# DC-DC_-5V.net
KiCad netlist of a schematic drawn in Altium Designer
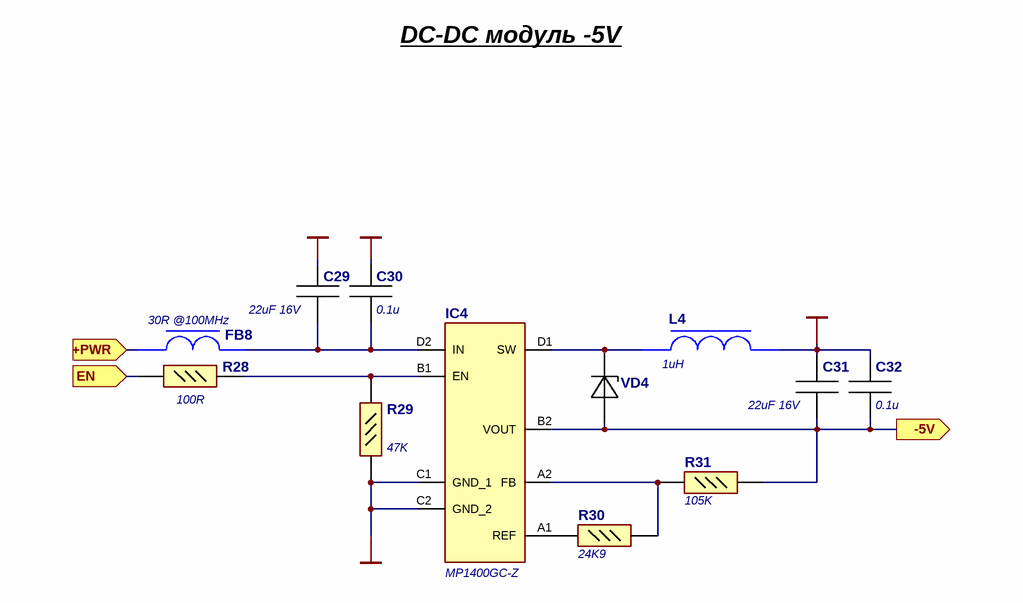
[diagram p0: DC-DC модуль -5V.SchDoc]

(export (version "E")
  (design (tool "Eeschema 10.0.6"))
  (components
    (comp (ref "C29")
      (value "22uF 16V")
      (footprint ":CAP0805 C2012X125")
      (description "CAP CER 22uF 16V X5R")
      (fields
        (field (name "MANUFACTURER_PART_NUMBER") "GRM21BR61C226ME44L")
        (field (name "MOUSER PART NUMBER") "81-GRM21BR61C226ME4L")
      )
      (libsource (lib "Capacitors 0805") (part "GRM21BR61C226ME44L"))
    )
    (comp (ref "C30")
      (value "0.1u")
      (footprint ":CAP0402 100x50x50")
      (description "±10% 25V Ceramic Capacitor X7R 0402 (1005 Metric)")
      (fields
        (field (name "MANUFACTURER_PART_NUMBER") "GRM155R71E104KE14J")
        (field (name "MOUSER PART NUMBER") "81-GRM155R71E104KE4J")
      )
      (libsource (lib "Capacitors 0402") (part "GRM155R71E104KE14J"))
    )
    (comp (ref "C31")
      (value "22uF 16V")
      (footprint ":CAP0805 C2012X125")
      (description "CAP CER 22uF 16V X5R")
      (fields
        (field (name "MANUFACTURER_PART_NUMBER") "GRM21BR61C226ME44L")
        (field (name "MOUSER PART NUMBER") "81-GRM21BR61C226ME4L")
      )
      (libsource (lib "Capacitors 0805") (part "GRM21BR61C226ME44L"))
    )
    (comp (ref "C32")
      (value "0.1u")
      (footprint ":CAP0402 100x50x50")
      (description "±10% 25V Ceramic Capacitor X7R 0402 (1005 Metric)")
      (fields
        (field (name "MANUFACTURER_PART_NUMBER") "GRM155R71E104KE14J")
        (field (name "MOUSER PART NUMBER") "81-GRM155R71E104KE4J")
      )
      (libsource (lib "Capacitors 0402") (part "GRM155R71E104KE14J"))
    )
    (comp (ref "FB8")
      (value "30R @100MHz")
      (footprint ":FER BLM18SP300SN1D")
      (description "30 Ohms @ 100MHz 1 Power Line Ferrite Bead 0603 (1608 Metric) 6A 8mOhm")
      (fields
        (field (name "MANUFACTURER_PART_NUMBER") "BLM18SP300SN1D")
        (field (name "MOUSER PART NUMBER") "81-BLM18SP300SN1D")
      )
      (libsource (lib "Ferrite Bead") (part "BLM18SP300SN1D"))
    )
    (comp (ref "IC4")
      (value "MP1400GC-Z")
      (footprint ":BGA8 CSP P2X4_80X160X63")
      (description "DC/DC Converter \r\nInput 2.7V...7V\r\nOutput -0.9V...-6V 600mA")
      (libsource (lib "DC-DC convertors") (part "MP1400GC-Z"))
    )
    (comp (ref "L4")
      (value "1uH")
      (footprint ":IND1210 C3225")
      (fields (field (name "MANUFACTURER_PART_NUMBER") "74479299210"))
      (libsource (lib "Inductance") (part "74479299210"))
    )
    (comp (ref "R28")
      (value "RC0402FR-07")
      (footprint ":RES0402")
      (fields (field (name "MANUFACTURER_PART_NUMBER (PART 2: VALUE)") "100R"))
      (libsource (lib "") (part "RC0402FR-07_1"))
    )
    (comp (ref "R29")
      (value "RC0402FR-07")
      (footprint ":RES0402")
      (fields (field (name "MANUFACTURER_PART_NUMBER (PART 2: VALUE)") "47K"))
      (libsource (lib "Resistors 0402") (part "RC0402FR-07"))
    )
    (comp (ref "R30")
      (value "RC0402FR-07")
      (footprint ":RES0402")
      (fields (field (name "MANUFACTURER_PART_NUMBER (PART 2: VALUE)") "24K9"))
      (libsource (lib "") (part "RC0402FR-07_1"))
    )
    (comp (ref "R31")
      (value "RC0402FR-07")
      (footprint ":RES0402")
      (fields (field (name "MANUFACTURER_PART_NUMBER (PART 2: VALUE)") "105K"))
      (libsource (lib "") (part "RC0402FR-07_1"))
    )
    (comp (ref "VD4")
      (value "40V 1.5A")
      (footprint ":DIODE CST2C")
      (description "Diode Schottky 40V 1.5A\r\n@If 550mV @ 1.5A\r\n@Vr 200µA @ 40V")
      (fields (field (name "MANUFACTURER_PART_NUMBER") "CCS15S40,L3F"))
      (libsource (lib "Diodes 0603") (part "CCS15S40,L3F"))
    )
  )
  (nets
    (net (code "1") (name "/+PWR") (class "Default")
      (node (ref "FB8") (pin "1") (pinfunction "1_1") (pintype "passive"))
    )
    (net (code "2") (name "/-5V") (class "Default")
      (node (ref "C31") (pin "1") (pinfunction "1_1") (pintype "passive"))
      (node (ref "C32") (pin "2") (pinfunction "2_2") (pintype "passive"))
      (node (ref "IC4") (pin "B2") (pinfunction "VOUT_B2") (pintype "passive"))
      (node (ref "R31") (pin "2") (pinfunction "2_2") (pintype "passive"))
      (node (ref "VD4") (pin "2") (pinfunction "A_2") (pintype "passive"))
    )
    (net (code "3") (name "/EN") (class "Default")
      (node (ref "R28") (pin "1") (pinfunction "1_1") (pintype "passive"))
    )
    (net (code "4") (name "GND") (class "Default")
      (node (ref "C29") (pin "2") (pinfunction "2_2") (pintype "passive"))
      (node (ref "C30") (pin "1") (pinfunction "1_1") (pintype "passive"))
      (node (ref "C31") (pin "2") (pinfunction "2_2") (pintype "passive"))
      (node (ref "C32") (pin "1") (pinfunction "1_1") (pintype "passive"))
      (node (ref "IC4") (pin "C1") (pinfunction "GND_1_C1") (pintype "passive"))
      (node (ref "IC4") (pin "C2") (pinfunction "GND_2_C2") (pintype "passive"))
      (node (ref "L4") (pin "2") (pinfunction "2_2") (pintype "passive"))
      (node (ref "R29") (pin "1") (pinfunction "1_1") (pintype "passive"))
    )
    (net (code "5") (name "Net-(IC4-EN)") (class "Default")
      (node (ref "IC4") (pin "B1") (pinfunction "EN_B1") (pintype "passive"))
      (node (ref "R28") (pin "2") (pinfunction "2_2") (pintype "passive"))
      (node (ref "R29") (pin "2") (pinfunction "2_2") (pintype "passive"))
    )
    (net (code "6") (name "Net-(IC4-FB)") (class "Default")
      (node (ref "IC4") (pin "A2") (pinfunction "FB_A2") (pintype "passive"))
      (node (ref "R30") (pin "2") (pinfunction "2_2") (pintype "passive"))
      (node (ref "R31") (pin "1") (pinfunction "1_1") (pintype "passive"))
    )
    (net (code "7") (name "Net-(IC4-IN)") (class "Default")
      (node (ref "C29") (pin "1") (pinfunction "1_1") (pintype "passive"))
      (node (ref "C30") (pin "2") (pinfunction "2_2") (pintype "passive"))
      (node (ref "FB8") (pin "2") (pinfunction "2_2") (pintype "passive"))
      (node (ref "IC4") (pin "D2") (pinfunction "IN_D2") (pintype "passive"))
    )
    (net (code "8") (name "Net-(IC4-REF)") (class "Default")
      (node (ref "IC4") (pin "A1") (pinfunction "REF_A1") (pintype "passive"))
      (node (ref "R30") (pin "1") (pinfunction "1_1") (pintype "passive"))
    )
    (net (code "9") (name "Net-(IC4-SW)") (class "Default")
      (node (ref "IC4") (pin "D1") (pinfunction "SW_D1") (pintype "passive"))
      (node (ref "L4") (pin "1") (pinfunction "1_1") (pintype "passive"))
      (node (ref "VD4") (pin "1") (pinfunction "K_1") (pintype "passive"))
    )
  )
)
